# EXT_U_DET.net
KiCad netlist of a schematic drawn in Altium Designer
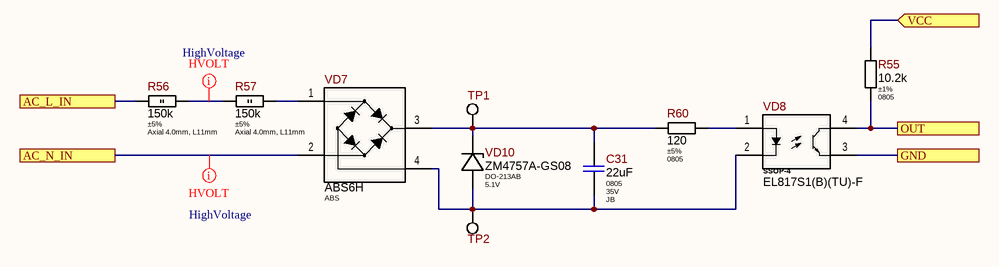
[diagram p0: EXT_U_DET.SchDoc]

(export (version "E")
  (design (tool "Eeschema 10.0.6"))
  (components
    (comp (ref "C31")
      (value "22uF")
      (footprint "CAP-0805(2012)X125T20")
      (description "22uF 35V JB ±20% 0805 Ceramic Capacitor RoHS")
      (fields
        (field (name "PACKAGE") "0805")
        (field (name "VOLTAGE") "35V")
        (field (name "DIELECTRIC TYPE") "JB")
        (field (name "PART NUMBER") "C2012JB1V226M125AC")
        (field (name "MANUFACTURER") "TDK Corporation")
      )
      (libsource (lib "capacitors") (part "C2012JB1V226M125AC"))
    )
    (comp (ref "R55")
      (value "10.2k")
      (footprint "R_ANY_CHIP_0805_MED")
      (description "10.2 kOhms ±1%, 1/8W 0805 Thick Film Resistor")
      (fields
        (field (name "TOLERANCE") "±1%")
        (field (name "PACKAGE") "0805")
        (field (name "PART NUMBER") "RC0805FR-0710K2L")
        (field (name "MANUFACTURER") "Yageo")
      )
      (libsource (lib "resistors") (part "RC0805FR-0710K2L"))
    )
    (comp (ref "R56")
      (value "150k")
      (footprint "MOR200S-Series")
      (description "150k Ohm ±5%, 2W d4.0mm L11mm Axial Through Hole, Metal Oxide Resistor, Al2O3")
      (fields
        (field (name "TOLERANCE") "±5%")
        (field (name "PACKAGE") "Axial 4.0mm, L11mm")
        (field (name "PART NUMBER") "MOR200SJTB-10R")
        (field (name "MANUFACTURER") "Hitano")
      )
      (libsource (lib "resistors") (part "MOR200SJTB-10R"))
    )
    (comp (ref "R57")
      (value "150k")
      (footprint "MOR200S-Series")
      (description "150k Ohm ±5%, 2W d4.0mm L11mm Axial Through Hole, Metal Oxide Resistor, Al2O3")
      (fields
        (field (name "TOLERANCE") "±5%")
        (field (name "PACKAGE") "Axial 4.0mm, L11mm")
        (field (name "PART NUMBER") "MOR200SJTB-10R")
        (field (name "MANUFACTURER") "Hitano")
      )
      (libsource (lib "resistors") (part "MOR200SJTB-10R"))
    )
    (comp (ref "R60")
      (value "120")
      (footprint "R_ANY_CHIP_0805_MED")
      (description "120 Ohms ±5%, 1/2W 0805 Thick Film Resistor")
      (fields
        (field (name "TOLERANCE") "±5%")
        (field (name "PACKAGE") "0805")
        (field (name "PART NUMBER") "ERJ-P06J121V")
        (field (name "MANUFACTURER") "Yageo")
      )
      (libsource (lib "resistors") (part "ERJ-P06J121V"))
    )
    (comp (ref "TP1")
      (value "PAD-0.96mm")
      (footprint "PAD-0.96mm")
      (description "0.96mm Pad for Plug-In or Receptacle")
      (fields (field (name "MANUFACTURER") "NONE"))
      (libsource (lib "probetools") (part "PAD-0.96mm"))
    )
    (comp (ref "TP2")
      (value "PAD-0.96mm")
      (footprint "PAD-0.96mm")
      (description "0.96mm Pad for Plug-In or Receptacle")
      (fields (field (name "MANUFACTURER") "NONE"))
      (libsource (lib "probetools") (part "PAD-0.96mm"))
    )
    (comp (ref "VD7")
      (value "ABS6H")
      (footprint "ABSxx-Series")
      (description "1A, 600V Standard Bridge Rectifier, ABS Package")
      (fields
        (field (name "PART NUMBER") "ABS6H")
        (field (name "PACKAGE") "ABS")
        (field (name "MANUFACTURER") "Taiwan Semiconductor")
        (field (name "VOLTAGE") "600V")
      )
      (libsource (lib "diodes") (part "ABS6H"))
    )
    (comp (ref "VD8")
      (value "EL817S1(B)(TU)-F")
      (footprint "EL-817S1-(x)(xx)")
      (description "1-Channel Photocoupler, 5kV, 130-260% CTR, SSOP-4")
      (fields
        (field (name "PACKAGE") "SSOP-4")
        (field (name "PART NUMBER") "EL817S1(B)(TU)-F")
        (field (name "MANUFACTURER") "Everlight Electronics")
      )
      (libsource (lib "opto") (part "EL817S1(B)(TU)-F"))
    )
    (comp (ref "VD10")
      (value "ZM4757A-GS08")
      (footprint "DO-213AB")
      (description "Zener Diode 5.1V, 1W, ±5%, 5uA Reverse Current, DO-213AB")
      (fields
        (field (name "PART NUMBER") "ZM4757A-GS08")
        (field (name "PACKAGE") "DO-213AB")
        (field (name "VOLTAGE") "5.1V")
        (field (name "MANUFACTURER") "Vishay Semiconductor")
      )
      (libsource (lib "diodes") (part "ZM4757A-GS08"))
    )
  )
  (nets
    (net (code "1") (name "/AC_L_IN") (class "Default") (node (ref "R56") (pin "1") (pintype "passive")))
    (net (code "2") (name "/AC_N_IN") (class "Default")
      (node (ref "VD7") (pin "2") (pinfunction "~_2") (pintype "passive"))
    )
    (net (code "3") (name "/GND") (class "Default")
      (node (ref "VD8") (pin "3") (pinfunction "Emitter_3") (pintype "passive"))
    )
    (net (code "4") (name "/OUT") (class "Default")
      (node (ref "R55") (pin "2") (pintype "passive"))
      (node (ref "VD8") (pin "4") (pinfunction "Collector_4") (pintype "passive"))
    )
    (net (code "5") (name "/VCC") (class "Default") (node (ref "R55") (pin "1") (pintype "passive")))
    (net (code "6") (name "Net-(R56-Pad2)") (class "Default")
      (node (ref "R56") (pin "2") (pintype "passive"))
      (node (ref "R57") (pin "1") (pintype "passive"))
    )
    (net (code "7") (name "Net-(R57-Pad2)") (class "Default")
      (node (ref "R57") (pin "2") (pintype "passive"))
      (node (ref "VD7") (pin "1") (pinfunction "~_1") (pintype "passive"))
    )
    (net (code "8") (name "Net-(VD7-+)") (class "Default")
      (node (ref "C31") (pin "1") (pinfunction "1_1") (pintype "passive"))
      (node (ref "R60") (pin "1") (pintype "passive"))
      (node (ref "TP1") (pin "1") (pintype "passive"))
      (node (ref "VD10") (pin "CA") (pintype "passive"))
      (node (ref "VD7") (pin "3") (pinfunction "+_3") (pintype "passive"))
    )
    (net (code "9") (name "Net-(VD7--)") (class "Default")
      (node (ref "C31") (pin "2") (pinfunction "2_2") (pintype "passive"))
      (node (ref "TP2") (pin "1") (pintype "passive"))
      (node (ref "VD10") (pin "AN") (pintype "passive"))
      (node (ref "VD7") (pin "4") (pinfunction "-_4") (pintype "passive"))
      (node (ref "VD8") (pin "2") (pinfunction "Cathode_2") (pintype "passive"))
    )
    (net (code "10") (name "Net-(VD8-Anode)") (class "Default")
      (node (ref "R60") (pin "2") (pintype "passive"))
      (node (ref "VD8") (pin "1") (pinfunction "Anode_1") (pintype "passive"))
    )
  )
)
